# SCH_Sun-Blinking-Board_2025-11-20.net
KiCad netlist of a schematic drawn in EasyEDA
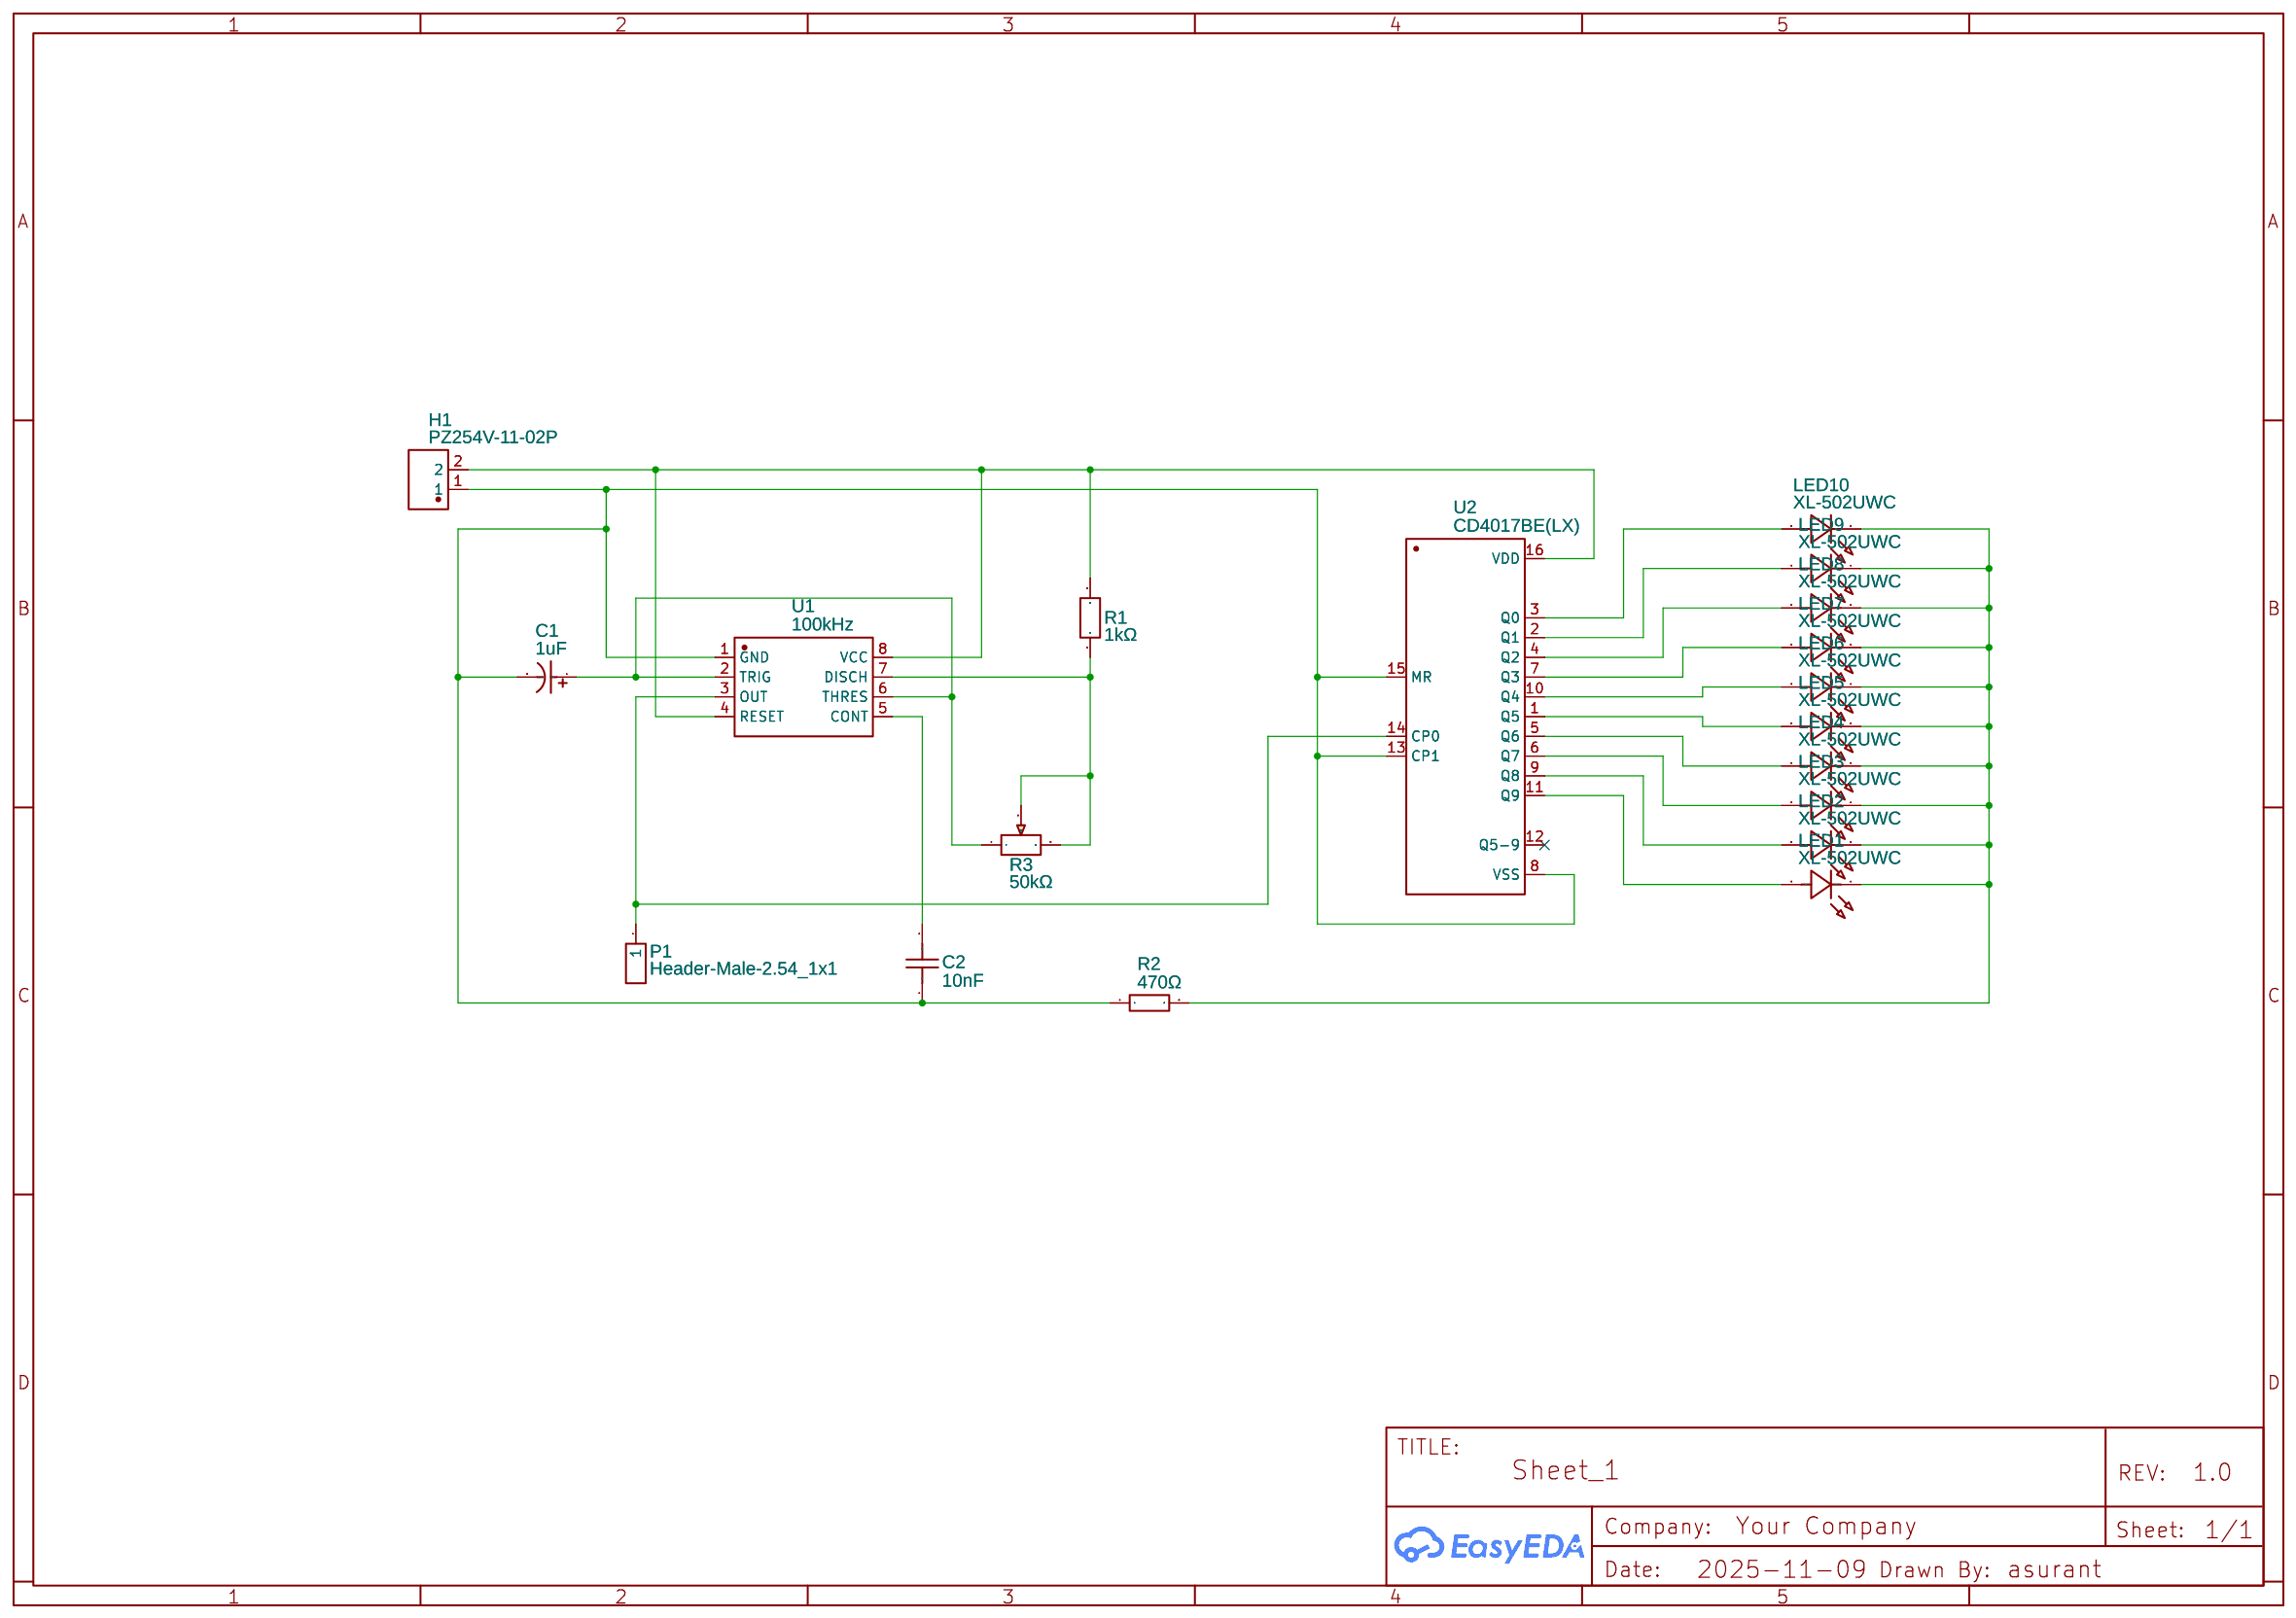
[diagram p0: schematic sheet]

(export (version "E")
  (design (tool "Eeschema 10.0.6"))
  (components
    (comp (ref "C1")
      (value "1uF")
      (fields (field (name "Manufacturer Part") "KF010M050C110A") (field (name "Manufacturer") "CapXon(丰宾)"))
      (libsource (lib "") (part "KF010M050C110A"))
    )
    (comp (ref "C2")
      (value "10nF")
      (fields (field (name "Manufacturer Part") "N09F1B103MN0B0S0N0") (field (name "Manufacturer") "STE(松田)"))
      (libsource (lib "") (part "N09F1B103MN0B0S0N0"))
    )
    (comp (ref "H1")
      (value "PZ254V-11-02P")
      (fields (field (name "Manufacturer") "XFCN(兴飞)"))
      (libsource (lib "") (part "PZ254V-11-02P"))
    )
    (comp (ref "LED1")
      (value "XL-502UWC")
      (fields (field (name "Manufacturer") "XINGLIGHT(成兴光)"))
      (libsource (lib "") (part "XL-502UWC"))
    )
    (comp (ref "LED2")
      (value "XL-502UWC")
      (fields (field (name "Manufacturer") "XINGLIGHT(成兴光)"))
      (libsource (lib "") (part "XL-502UWC"))
    )
    (comp (ref "LED3")
      (value "XL-502UWC")
      (fields (field (name "Manufacturer") "XINGLIGHT(成兴光)"))
      (libsource (lib "") (part "XL-502UWC"))
    )
    (comp (ref "LED4")
      (value "XL-502UWC")
      (fields (field (name "Manufacturer") "XINGLIGHT(成兴光)"))
      (libsource (lib "") (part "XL-502UWC"))
    )
    (comp (ref "LED5")
      (value "XL-502UWC")
      (fields (field (name "Manufacturer") "XINGLIGHT(成兴光)"))
      (libsource (lib "") (part "XL-502UWC"))
    )
    (comp (ref "LED6")
      (value "XL-502UWC")
      (fields (field (name "Manufacturer") "XINGLIGHT(成兴光)"))
      (libsource (lib "") (part "XL-502UWC"))
    )
    (comp (ref "LED7")
      (value "XL-502UWC")
      (fields (field (name "Manufacturer") "XINGLIGHT(成兴光)"))
      (libsource (lib "") (part "XL-502UWC"))
    )
    (comp (ref "LED8")
      (value "XL-502UWC")
      (fields (field (name "Manufacturer") "XINGLIGHT(成兴光)"))
      (libsource (lib "") (part "XL-502UWC"))
    )
    (comp (ref "LED9")
      (value "XL-502UWC")
      (fields (field (name "Manufacturer") "XINGLIGHT(成兴光)"))
      (libsource (lib "") (part "XL-502UWC"))
    )
    (comp (ref "LED10")
      (value "XL-502UWC")
      (fields (field (name "Manufacturer") "XINGLIGHT(成兴光)"))
      (libsource (lib "") (part "XL-502UWC"))
    )
    (comp (ref "P1")
      (value "Header-Male-2.54_1x1")
      (fields (field (name "Manufacturer Part") "2.54-1*1P针") (field (name "Manufacturer") "BOOMELE(博穆精密)"))
      (libsource (lib "") (part "Header-Male-2.54_1x1"))
    )
    (comp (ref "R1")
      (value "1kΩ")
      (fields (field (name "Manufacturer Part") "MF1/4W-1KΩ±1%T52") (field (name "Manufacturer") "华星机电"))
      (libsource (lib "") (part "MF1/4W-1KΩ±1%T52"))
    )
    (comp (ref "R2")
      (value "470Ω")
      (fields
        (field (name "Manufacturer Part") "MFR0W4F4700A50")
        (field (name "Manufacturer") "UNI-ROYAL(厚声)")
      )
      (libsource (lib "") (part "MFR0W4F4700A50"))
    )
    (comp (ref "R3")
      (value "50kΩ")
      (fields (field (name "Manufacturer Part") "3296X-1-503") (field (name "Manufacturer") "BOCHEN(博晨)"))
      (libsource (lib "") (part "3296X-1-503_C118912"))
    )
    (comp (ref "U1")
      (value "100kHz")
      (fields (field (name "Manufacturer Part") "NE555P") (field (name "Manufacturer") "TI(德州仪器)"))
      (libsource (lib "") (part "NE555P"))
    )
    (comp (ref "U2")
      (value "CD4017BE(LX)")
      (fields (field (name "Manufacturer") "LX(灵星芯微)"))
      (libsource (lib "") (part "CD4017BE(LX)"))
    )
  )
  (nets
    (net (code "1") (name "Net-(LED1-A)") (class "Default")
      (node (ref "LED1") (pin "2") (pinfunction "A_2") (pintype "unspecified"))
      (node (ref "U2") (pin "11") (pinfunction "Q9_11") (pintype "unspecified"))
    )
    (net (code "2") (name "Net-(LED1-K)") (class "Default")
      (node (ref "LED1") (pin "1") (pinfunction "K_1") (pintype "unspecified"))
      (node (ref "LED10") (pin "1") (pinfunction "K_1") (pintype "unspecified"))
      (node (ref "LED2") (pin "1") (pinfunction "K_1") (pintype "unspecified"))
      (node (ref "LED3") (pin "1") (pinfunction "K_1") (pintype "unspecified"))
      (node (ref "LED4") (pin "1") (pinfunction "K_1") (pintype "unspecified"))
      (node (ref "LED5") (pin "1") (pinfunction "K_1") (pintype "unspecified"))
      (node (ref "LED6") (pin "1") (pinfunction "K_1") (pintype "unspecified"))
      (node (ref "LED7") (pin "1") (pinfunction "K_1") (pintype "unspecified"))
      (node (ref "LED8") (pin "1") (pinfunction "K_1") (pintype "unspecified"))
      (node (ref "LED9") (pin "1") (pinfunction "K_1") (pintype "unspecified"))
      (node (ref "R2") (pin "2") (pinfunction "2_2") (pintype "input"))
    )
    (net (code "3") (name "Net-(LED2-A)") (class "Default")
      (node (ref "LED2") (pin "2") (pinfunction "A_2") (pintype "unspecified"))
      (node (ref "U2") (pin "9") (pinfunction "Q8_9") (pintype "unspecified"))
    )
    (net (code "4") (name "Net-(LED3-A)") (class "Default")
      (node (ref "LED3") (pin "2") (pinfunction "A_2") (pintype "unspecified"))
      (node (ref "U2") (pin "6") (pinfunction "Q7_6") (pintype "unspecified"))
    )
    (net (code "5") (name "Net-(LED4-A)") (class "Default")
      (node (ref "LED4") (pin "2") (pinfunction "A_2") (pintype "unspecified"))
      (node (ref "U2") (pin "5") (pinfunction "Q6_5") (pintype "unspecified"))
    )
    (net (code "6") (name "Net-(LED5-A)") (class "Default")
      (node (ref "LED5") (pin "2") (pinfunction "A_2") (pintype "unspecified"))
      (node (ref "U2") (pin "1") (pinfunction "Q5_1") (pintype "unspecified"))
    )
    (net (code "7") (name "Net-(LED6-A)") (class "Default")
      (node (ref "LED6") (pin "2") (pinfunction "A_2") (pintype "unspecified"))
      (node (ref "U2") (pin "10") (pinfunction "Q4_10") (pintype "unspecified"))
    )
    (net (code "8") (name "Net-(LED7-A)") (class "Default")
      (node (ref "LED7") (pin "2") (pinfunction "A_2") (pintype "unspecified"))
      (node (ref "U2") (pin "7") (pinfunction "Q3_7") (pintype "unspecified"))
    )
    (net (code "9") (name "Net-(LED8-A)") (class "Default")
      (node (ref "LED8") (pin "2") (pinfunction "A_2") (pintype "unspecified"))
      (node (ref "U2") (pin "4") (pinfunction "Q2_4") (pintype "unspecified"))
    )
    (net (code "10") (name "Net-(LED9-A)") (class "Default")
      (node (ref "LED9") (pin "2") (pinfunction "A_2") (pintype "unspecified"))
      (node (ref "U2") (pin "2") (pinfunction "Q1_2") (pintype "unspecified"))
    )
    (net (code "11") (name "Net-(LED10-A)") (class "Default")
      (node (ref "LED10") (pin "2") (pinfunction "A_2") (pintype "unspecified"))
      (node (ref "U2") (pin "3") (pinfunction "Q0_3") (pintype "unspecified"))
    )
    (net (code "12") (name "Net-(U1-CONT)") (class "Default")
      (node (ref "C2") (pin "2") (pinfunction "2_2") (pintype "unspecified"))
      (node (ref "U1") (pin "5") (pinfunction "CONT_5") (pintype "unspecified"))
    )
    (net (code "13") (name "Net-(U1-DISCH)") (class "Default")
      (node (ref "R1") (pin "1") (pinfunction "1_1") (pintype "unspecified"))
      (node (ref "R3") (pin "2") (pinfunction "2_2") (pintype "input"))
      (node (ref "R3") (pin "3") (pinfunction "3_3") (pintype "input"))
      (node (ref "U1") (pin "7") (pinfunction "DISCH_7") (pintype "unspecified"))
    )
    (net (code "14") (name "Net-(U1-GND)") (class "Default")
      (node (ref "C1") (pin "2") (pinfunction "2_2") (pintype "input"))
      (node (ref "C2") (pin "1") (pinfunction "1_1") (pintype "unspecified"))
      (node (ref "H1") (pin "1") (pinfunction "1_1") (pintype "unspecified"))
      (node (ref "R2") (pin "1") (pinfunction "1_1") (pintype "input"))
      (node (ref "U1") (pin "1") (pinfunction "GND_1") (pintype "unspecified"))
      (node (ref "U2") (pin "13") (pinfunction "CP1_13") (pintype "unspecified"))
      (node (ref "U2") (pin "15") (pinfunction "MR_15") (pintype "unspecified"))
      (node (ref "U2") (pin "8") (pinfunction "VSS_8") (pintype "unspecified"))
    )
    (net (code "15") (name "Net-(U1-OUT)") (class "Default")
      (node (ref "P1") (pin "1") (pinfunction "1_1") (pintype "input"))
      (node (ref "U1") (pin "3") (pinfunction "OUT_3") (pintype "unspecified"))
      (node (ref "U2") (pin "14") (pinfunction "CP0_14") (pintype "unspecified"))
    )
    (net (code "16") (name "Net-(U1-RESET)") (class "Default")
      (node (ref "H1") (pin "2") (pinfunction "2_2") (pintype "unspecified"))
      (node (ref "R1") (pin "2") (pinfunction "2_2") (pintype "unspecified"))
      (node (ref "U1") (pin "4") (pinfunction "RESET_4") (pintype "unspecified"))
      (node (ref "U1") (pin "8") (pinfunction "VCC_8") (pintype "unspecified"))
      (node (ref "U2") (pin "16") (pinfunction "VDD_16") (pintype "unspecified"))
    )
    (net (code "17") (name "Net-(U1-THRES)") (class "Default")
      (node (ref "C1") (pin "1") (pinfunction "1_1") (pintype "input"))
      (node (ref "R3") (pin "1") (pinfunction "1_1") (pintype "input"))
      (node (ref "U1") (pin "2") (pinfunction "TRIG_2") (pintype "unspecified"))
      (node (ref "U1") (pin "6") (pinfunction "THRES_6") (pintype "unspecified"))
    )
    (net (code "18") (name "unconnected-(U2-Q5-9-Pad12)") (class "Default")
      (node (ref "U2") (pin "12") (pinfunction "Q5-9_12") (pintype "unspecified+no_connect"))
    )
  )
)
